# RoverWing-V1_3sch.net
KiCad netlist of a schematic drawn in EAGLE
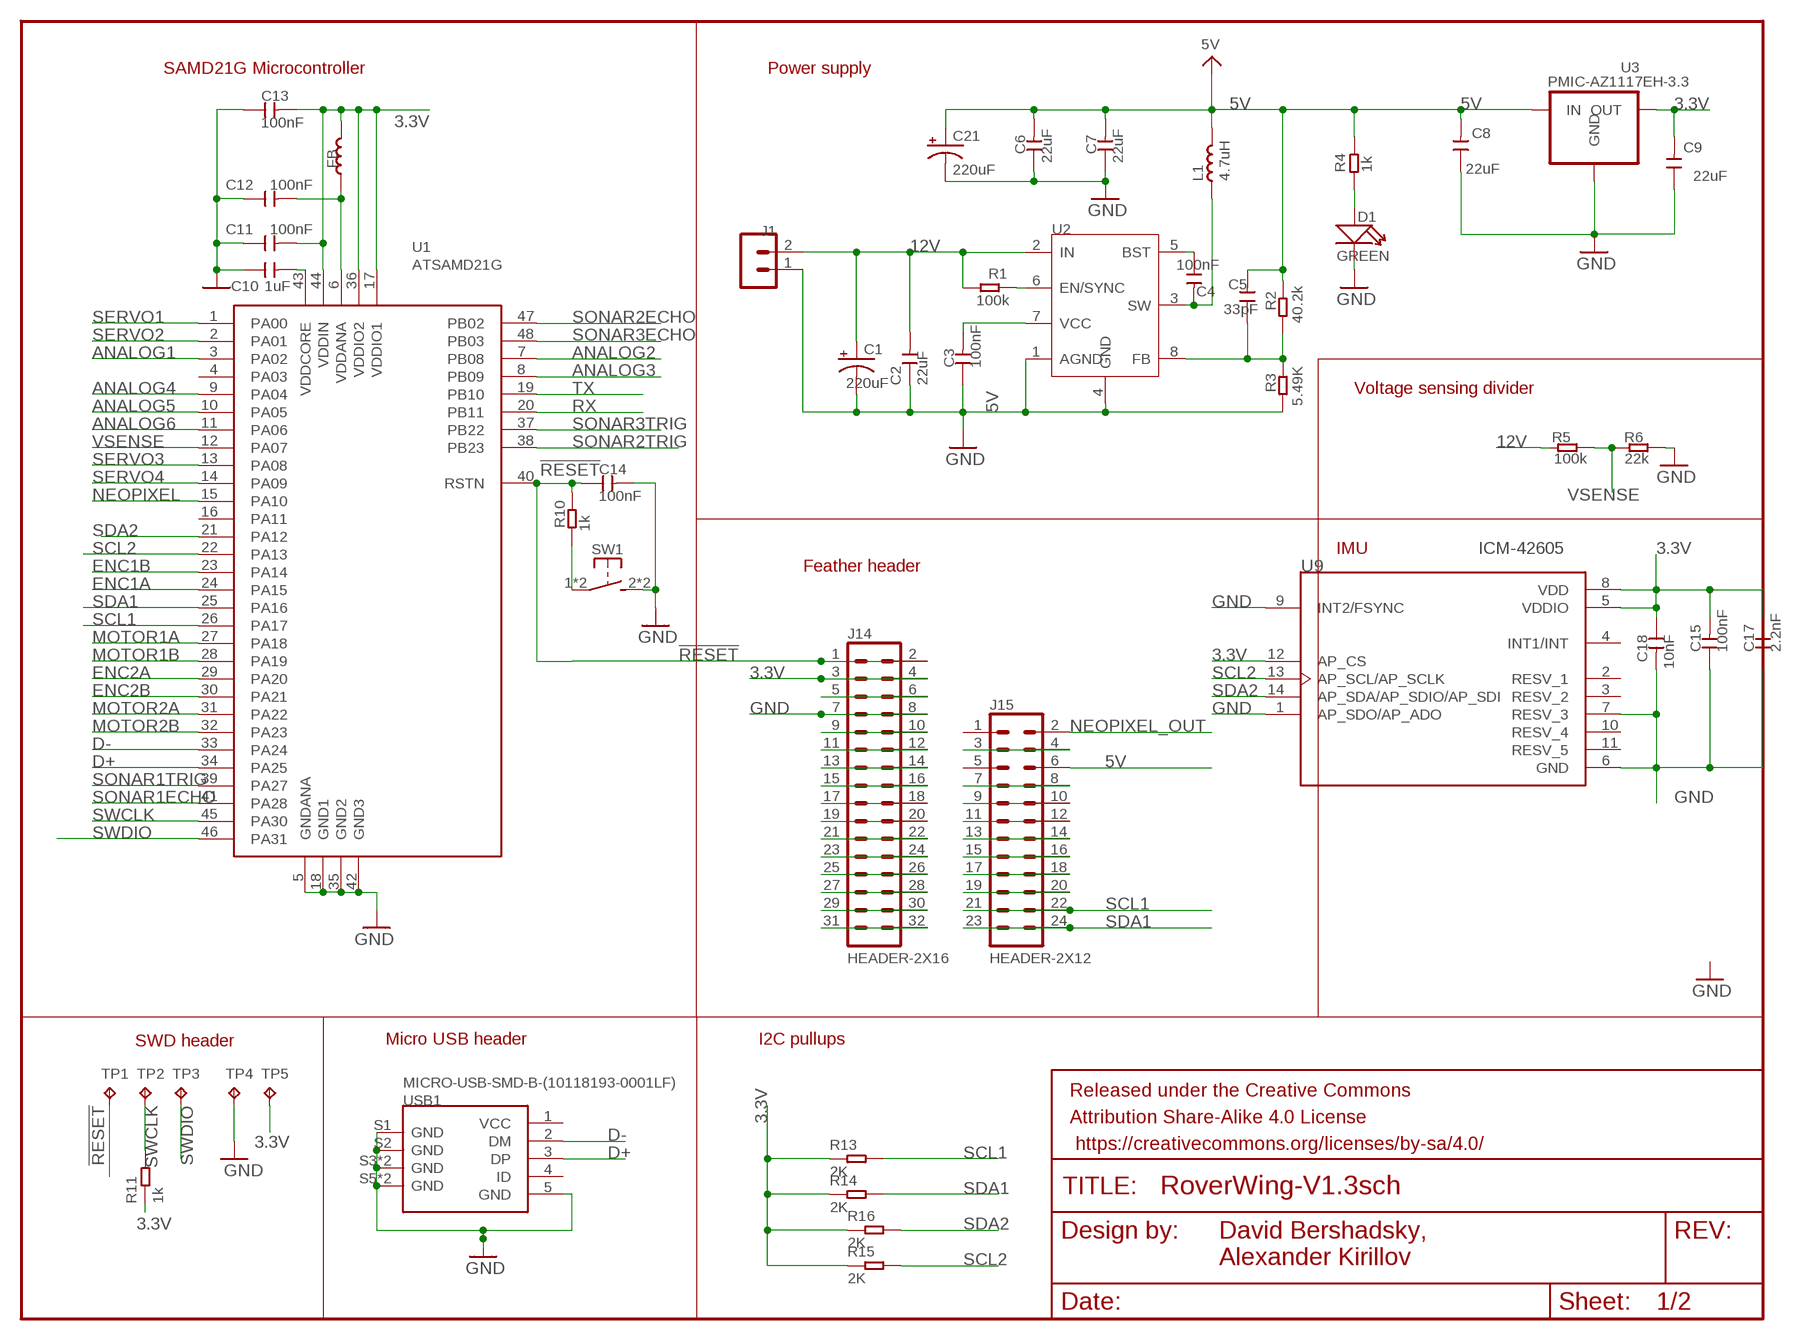
[diagram p0: schematic, sheet 1]
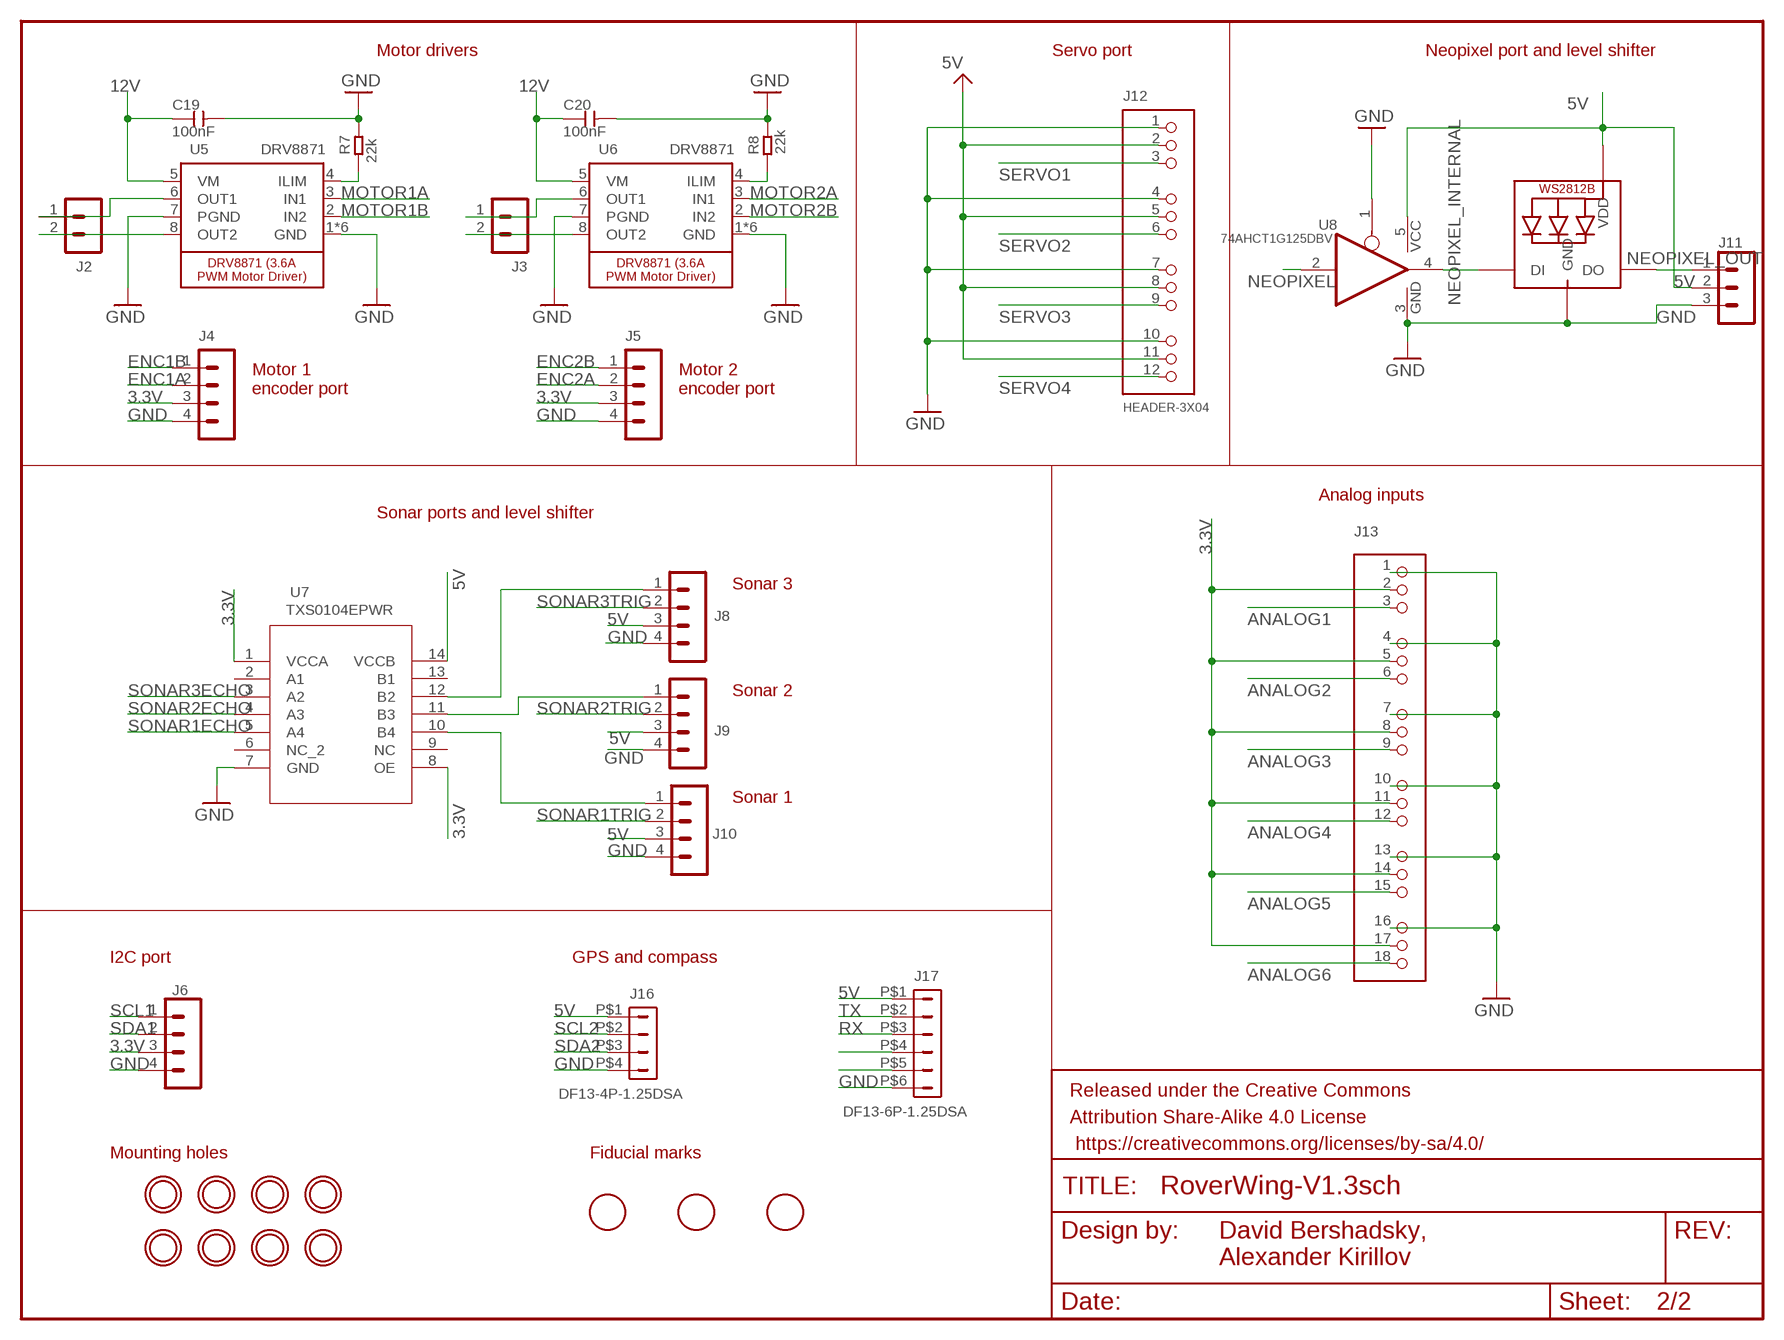
[diagram p1: schematic, sheet 2]

(export (version "E")
  (design (tool "Eeschema 10.0.6"))
  (components
    (comp (ref "C19")
      (value "100nF")
      (footprint "eagle-import:0805")
      (libsource (lib "eagle-import") (part "CAP-CERAMIC-SMD0805"))
    )
    (comp (ref "C20")
      (value "100nF")
      (footprint "eagle-import:0805")
      (libsource (lib "eagle-import") (part "CAP-CERAMIC-SMD0805"))
    )
    (comp (ref "D2")
      (value "WS2812B3535")
      (footprint "eagle-import:LED3535")
      (fields (field (name "MANUFACTURER") "Worldsemi") (field (name "PARTNO") "WS2812B-3535 "))
      (libsource (lib "eagle-import") (part "WS2812B3535"))
    )
    (comp (ref "FRAME1")
      (value "FRAME-LETTERNO_PACKAGE")
      (footprint "eagle-import:DUMMY")
      (libsource (lib "eagle-import") (part "FRAME-LETTERNO_PACKAGE"))
    )
    (comp (ref "J2")
      (value "HEADER-VH")
      (footprint "eagle-import:B2P-VH")
      (fields (field (name "PARTNO") "B2P-VH(LF)(SN)  "))
      (libsource (lib "eagle-import") (part "HEADER-VH"))
    )
    (comp (ref "J3")
      (value "HEADER-VH")
      (footprint "eagle-import:B2P-VH")
      (fields (field (name "PARTNO") "B2P-VH(LF)(SN)  "))
      (libsource (lib "eagle-import") (part "HEADER-VH"))
    )
    (comp (ref "J4")
      (value "HEADER-PH-4P")
      (footprint "eagle-import:B4B-PH-K")
      (fields (field (name "PARTNO") "B4B-PH-K-S(LF)(SN)"))
      (libsource (lib "eagle-import") (part "HEADER-PH-4P"))
    )
    (comp (ref "J5")
      (value "HEADER-PH-4P")
      (footprint "eagle-import:B4B-PH-K")
      (fields (field (name "PARTNO") "B4B-PH-K-S(LF)(SN)"))
      (libsource (lib "eagle-import") (part "HEADER-PH-4P"))
    )
    (comp (ref "J6")
      (value "HEADER-PH-4P")
      (footprint "eagle-import:B4B-PH-K")
      (fields (field (name "PARTNO") "B4B-PH-K-S(LF)(SN)"))
      (libsource (lib "eagle-import") (part "HEADER-PH-4P"))
    )
    (comp (ref "J8")
      (value "HEADER-PH-4P")
      (footprint "eagle-import:B4B-PH-K")
      (fields (field (name "PARTNO") "B4B-PH-K-S(LF)(SN)"))
      (libsource (lib "eagle-import") (part "HEADER-PH-4P"))
    )
    (comp (ref "J9")
      (value "HEADER-PH-4P")
      (footprint "eagle-import:B4B-PH-K")
      (fields (field (name "PARTNO") "B4B-PH-K-S(LF)(SN)"))
      (libsource (lib "eagle-import") (part "HEADER-PH-4P"))
    )
    (comp (ref "J10")
      (value "HEADER-PH-4P")
      (footprint "eagle-import:B4B-PH-K")
      (fields (field (name "PARTNO") "B4B-PH-K-S(LF)(SN)"))
      (libsource (lib "eagle-import") (part "HEADER-PH-4P"))
    )
    (comp (ref "J11")
      (value "HEADER-PH-3P")
      (footprint "eagle-import:B3B-PH-K")
      (fields (field (name "PARTNO") "B3B-PH-K-S(LF)(SN)"))
      (libsource (lib "eagle-import") (part "HEADER-PH-3P"))
    )
    (comp (ref "J12")
      (value "HEADER-3X04")
      (footprint "eagle-import:3X04")
      (libsource (lib "eagle-import") (part "HEADER-3X04"))
    )
    (comp (ref "J13")
      (value "HEADER-3X06\"")
      (footprint "eagle-import:3X06")
      (libsource (lib "eagle-import") (part "HEADER-3X06{dblquote}"))
    )
    (comp (ref "J16")
      (value "DF13-4P-1.25DSA")
      (footprint "eagle-import:DF13-4P-1.25DSA")
      (libsource (lib "eagle-import") (part "DF13-4P-1.25DSA"))
    )
    (comp (ref "J17")
      (value "DF13-6P-1.25DSA")
      (footprint "eagle-import:DF13-6P-1.25DSA")
      (libsource (lib "eagle-import") (part "DF13-6P-1.25DSA"))
    )
    (comp (ref "R7")
      (value "22k")
      (footprint "eagle-import:0805")
      (libsource (lib "eagle-import") (part "RES-SMD-0805"))
    )
    (comp (ref "R8")
      (value "22k")
      (footprint "eagle-import:0805")
      (libsource (lib "eagle-import") (part "RES-SMD-0805"))
    )
    (comp (ref "U$3")
      (value "MOUNTINGHOLE3.0_NPH")
      (footprint "eagle-import:MOUNTINGHOLE_3.0_NPH")
      (libsource (lib "eagle-import") (part "MOUNTINGHOLE3.0_NPH"))
    )
    (comp (ref "U$4")
      (value "MOUNTINGHOLE3.0_NPH")
      (footprint "eagle-import:MOUNTINGHOLE_3.0_NPH")
      (libsource (lib "eagle-import") (part "MOUNTINGHOLE3.0_NPH"))
    )
    (comp (ref "U$11")
      (value "FIDUCIAL")
      (footprint "eagle-import:FIDUCIAL_1MM")
      (libsource (lib "eagle-import") (part "FIDUCIAL"))
    )
    (comp (ref "U$13")
      (value "FIDUCIAL")
      (footprint "eagle-import:FIDUCIAL_1MM")
      (libsource (lib "eagle-import") (part "FIDUCIAL"))
    )
    (comp (ref "U$14")
      (value "MOUNTINGHOLE3.0_NPH")
      (footprint "eagle-import:MOUNTINGHOLE_3.0_NPH")
      (libsource (lib "eagle-import") (part "MOUNTINGHOLE3.0_NPH"))
    )
    (comp (ref "U$15")
      (value "MOUNTINGHOLE3.0_NPH")
      (footprint "eagle-import:MOUNTINGHOLE_3.0_NPH")
      (libsource (lib "eagle-import") (part "MOUNTINGHOLE3.0_NPH"))
    )
    (comp (ref "U$17")
      (value "FIDUCIAL")
      (footprint "eagle-import:FIDUCIAL_1MM")
      (libsource (lib "eagle-import") (part "FIDUCIAL"))
    )
    (comp (ref "U$24")
      (value "MOUNTINGHOLE3.0_NPH")
      (footprint "eagle-import:MOUNTINGHOLE_3.0_NPH")
      (libsource (lib "eagle-import") (part "MOUNTINGHOLE3.0_NPH"))
    )
    (comp (ref "U$25")
      (value "MOUNTINGHOLE3.0_NPH")
      (footprint "eagle-import:MOUNTINGHOLE_3.0_NPH")
      (libsource (lib "eagle-import") (part "MOUNTINGHOLE3.0_NPH"))
    )
    (comp (ref "U$26")
      (value "MOUNTINGHOLE3.0_NPH")
      (footprint "eagle-import:MOUNTINGHOLE_3.0_NPH")
      (libsource (lib "eagle-import") (part "MOUNTINGHOLE3.0_NPH"))
    )
    (comp (ref "U$27")
      (value "MOUNTINGHOLE3.0_NPH")
      (footprint "eagle-import:MOUNTINGHOLE_3.0_NPH")
      (libsource (lib "eagle-import") (part "MOUNTINGHOLE3.0_NPH"))
    )
    (comp (ref "U5")
      (value "DRV8871")
      (footprint "eagle-import:HSOP8")
      (fields (field (name "MANUFACTURER") "TEXAS INSTRUMENTS") (field (name "PARTNO") "DRV8871DDAR"))
      (libsource (lib "eagle-import") (part "DRV8871"))
    )
    (comp (ref "U6")
      (value "DRV8871")
      (footprint "eagle-import:HSOP8")
      (fields (field (name "MANUFACTURER") "TEXAS INSTRUMENTS") (field (name "PARTNO") "DRV8871DDAR"))
      (libsource (lib "eagle-import") (part "DRV8871"))
    )
    (comp (ref "U7")
      (value "TXS0104EPWR")
      (footprint "eagle-import:PW14")
      (fields (field (name "MANUFACTURER") "Texas Instruments"))
      (libsource (lib "eagle-import") (part "TXS0104EPWR"))
    )
    (comp (ref "U8")
      (value "74AHCT1G125DBV")
      (footprint "eagle-import:SOT23-5")
      (fields (field (name "PARTNO") "SN74AHCT1G125DBVR"))
      (libsource (lib "eagle-import") (part "741G125DBVAHCT"))
    )
    (comp (ref "C1")
      (value "220uF")
      (footprint "eagle-import:CAP-8X10.5")
      (libsource (lib "eagle-import") (part "CAP-POL-SMD-8X10.5"))
    )
    (comp (ref "C2")
      (value "22uF")
      (footprint "eagle-import:0805")
      (libsource (lib "eagle-import") (part "CAP-CERAMIC-SMD0805"))
    )
    (comp (ref "C3")
      (value "100nF")
      (footprint "eagle-import:0805")
      (libsource (lib "eagle-import") (part "CAP-CERAMIC-SMD0805"))
    )
    (comp (ref "C4")
      (value "100nF")
      (footprint "eagle-import:0805")
      (libsource (lib "eagle-import") (part "CAP-CERAMIC-SMD0805"))
    )
    (comp (ref "C5")
      (value "33pF")
      (footprint "eagle-import:0805")
      (libsource (lib "eagle-import") (part "CAP-CERAMIC-SMD0805"))
    )
    (comp (ref "C6")
      (value "22uF")
      (footprint "eagle-import:0805")
      (libsource (lib "eagle-import") (part "CAP-CERAMIC-SMD0805"))
    )
    (comp (ref "C7")
      (value "22uF")
      (footprint "eagle-import:0805")
      (libsource (lib "eagle-import") (part "CAP-CERAMIC-SMD0805"))
    )
    (comp (ref "C8")
      (value "22uF")
      (footprint "eagle-import:0805")
      (libsource (lib "eagle-import") (part "CAP-CERAMIC-SMD0805"))
    )
    (comp (ref "C9")
      (value "22uF")
      (footprint "eagle-import:0805")
      (libsource (lib "eagle-import") (part "CAP-CERAMIC-SMD0805"))
    )
    (comp (ref "C10")
      (value "1uF")
      (footprint "eagle-import:0805")
      (libsource (lib "eagle-import") (part "CAP-CERAMIC-SMD0805"))
    )
    (comp (ref "C11")
      (value "100nF")
      (footprint "eagle-import:0805")
      (libsource (lib "eagle-import") (part "CAP-CERAMIC-SMD0805"))
    )
    (comp (ref "C12")
      (value "100nF")
      (footprint "eagle-import:0805")
      (libsource (lib "eagle-import") (part "CAP-CERAMIC-SMD0805"))
    )
    (comp (ref "C13")
      (value "100nF")
      (footprint "eagle-import:0805")
      (libsource (lib "eagle-import") (part "CAP-CERAMIC-SMD0805"))
    )
    (comp (ref "C14")
      (value "100nF")
      (footprint "eagle-import:0805")
      (libsource (lib "eagle-import") (part "CAP-CERAMIC-SMD0805"))
    )
    (comp (ref "C15")
      (value "100nF")
      (footprint "eagle-import:0805")
      (libsource (lib "eagle-import") (part "CAP-CERAMIC-SMD0805"))
    )
    (comp (ref "C17")
      (value "2.2nF")
      (footprint "eagle-import:0805")
      (libsource (lib "eagle-import") (part "CAP-CERAMIC-SMD0805"))
    )
    (comp (ref "C18")
      (value "10nF")
      (footprint "eagle-import:0805")
      (libsource (lib "eagle-import") (part "CAP-CERAMIC-SMD0805"))
    )
    (comp (ref "C21")
      (value "220uF")
      (footprint "eagle-import:CAP-6.3X5.4")
      (fields (field (name "PARTNO") "CS1E470M-CRE54 "))
      (libsource (lib "eagle-import") (part "CAP-POL-SMD-6.3X5.4"))
    )
    (comp (ref "D1")
      (value "GREEN")
      (footprint "eagle-import:LED-0805")
      (libsource (lib "eagle-import") (part "SMD-LED-0805"))
    )
    (comp (ref "FB")
      (value "330R-1500MA")
      (footprint "eagle-import:0805")
      (fields (field (name "PARTNO") "BLM21PG331SN1D"))
      (libsource (lib "eagle-import") (part "SMD-FERRITE-BEAD-330R-1500MA(0805)"))
    )
    (comp (ref "FRAME2")
      (value "FRAME-LETTERNO_PACKAGE")
      (footprint "eagle-import:DUMMY")
      (libsource (lib "eagle-import") (part "FRAME-LETTERNO_PACKAGE"))
    )
    (comp (ref "J1")
      (value "HEADER-VH")
      (footprint "eagle-import:B2P-VH")
      (fields (field (name "PARTNO") "B2P-VH(LF)(SN)  "))
      (libsource (lib "eagle-import") (part "HEADER-VH"))
    )
    (comp (ref "J14")
      (value "HEADER-2X16")
      (footprint "eagle-import:2X16")
      (libsource (lib "eagle-import") (part "HEADER-2X16"))
    )
    (comp (ref "J15")
      (value "HEADER-2X12")
      (footprint "eagle-import:2X12")
      (libsource (lib "eagle-import") (part "HEADER-2X12"))
    )
    (comp (ref "L1")
      (value "4.7uH")
      (footprint "eagle-import:IND_TDK_7.1X6.5")
      (fields (field (name "MANUFACTURER") "TDK") (field (name "PARTNO") "SPM6530T-4R7M "))
      (libsource (lib "eagle-import") (part "IND-TDK-SPM6530T"))
    )
    (comp (ref "R1")
      (value "100k")
      (footprint "eagle-import:0805")
      (libsource (lib "eagle-import") (part "RES-SMD-0805"))
    )
    (comp (ref "R2")
      (value "40.2k")
      (footprint "eagle-import:0805")
      (libsource (lib "eagle-import") (part "RES-SMD-0805"))
    )
    (comp (ref "R3")
      (value "5.49K")
      (footprint "eagle-import:0805")
      (libsource (lib "eagle-import") (part "RES-SMD-0805"))
    )
    (comp (ref "R4")
      (value "1k")
      (footprint "eagle-import:0805")
      (libsource (lib "eagle-import") (part "RES-SMD-0805"))
    )
    (comp (ref "R5")
      (value "100k")
      (footprint "eagle-import:0805")
      (libsource (lib "eagle-import") (part "RES-SMD-0805"))
    )
    (comp (ref "R6")
      (value "22k")
      (footprint "eagle-import:0805")
      (libsource (lib "eagle-import") (part "RES-SMD-0805"))
    )
    (comp (ref "R10")
      (value "1k")
      (footprint "eagle-import:0805")
      (libsource (lib "eagle-import") (part "RES-SMD-0805"))
    )
    (comp (ref "R11")
      (value "1k")
      (footprint "eagle-import:0805")
      (libsource (lib "eagle-import") (part "RES-SMD-0805"))
    )
    (comp (ref "R13")
      (value "2K")
      (footprint "eagle-import:R0603")
      (fields (field (name "MPN") "RC0603FR-071K8L"))
      (libsource (lib "eagle-import") (part "SMD-RES-1.8K-1%-1/10W(0603)"))
    )
    (comp (ref "R14")
      (value "2K")
      (footprint "eagle-import:R0603")
      (fields (field (name "MPN") "RC0603FR-071K8L"))
      (libsource (lib "eagle-import") (part "SMD-RES-1.8K-1%-1/10W(0603)"))
    )
    (comp (ref "R15")
      (value "2K")
      (footprint "eagle-import:R0603")
      (fields (field (name "MPN") "RC0603FR-071K8L"))
      (libsource (lib "eagle-import") (part "SMD-RES-1.8K-1%-1/10W(0603)"))
    )
    (comp (ref "R16")
      (value "2K")
      (footprint "eagle-import:R0603")
      (fields (field (name "MPN") "RC0603FR-071K8L"))
      (libsource (lib "eagle-import") (part "SMD-RES-1.8K-1%-1/10W(0603)"))
    )
    (comp (ref "SW1")
      (value "SW-TACTILE-4.5X4.5_SMD")
      (footprint "eagle-import:TL3305")
      (fields (field (name "MANUFACTURER") "BRIGHT") (field (name "PARTNO") "TSA453G38-250 "))
      (libsource (lib "eagle-import") (part "SW-TACTILE-4.5X4.5_SMD"))
    )
    (comp (ref "TP1")
      (value "TPTP15R")
      (footprint "eagle-import:TP15R")
      (libsource (lib "eagle-import") (part "TPTP15R"))
    )
    (comp (ref "TP2")
      (value "TPTP15R")
      (footprint "eagle-import:TP15R")
      (libsource (lib "eagle-import") (part "TPTP15R"))
    )
    (comp (ref "TP3")
      (value "TPTP15R")
      (footprint "eagle-import:TP15R")
      (libsource (lib "eagle-import") (part "TPTP15R"))
    )
    (comp (ref "TP4")
      (value "TPTP15R")
      (footprint "eagle-import:TP15R")
      (libsource (lib "eagle-import") (part "TPTP15R"))
    )
    (comp (ref "TP5")
      (value "TPTP15R")
      (footprint "eagle-import:TP15R")
      (libsource (lib "eagle-import") (part "TPTP15R"))
    )
    (comp (ref "U1")
      (value "ATSAMD21G")
      (footprint "eagle-import:TQFP-48-EDITED")
      (fields (field (name "MANUFACTURER") "Microchip Technology") (field (name "PARTNO") "ATSAMD21G18A-AU"))
      (libsource (lib "eagle-import") (part "ATSAMD21G"))
    )
    (comp (ref "U2")
      (value "MP2225")
      (footprint "eagle-import:SOT-23-8")
      (fields (field (name "MANUFACTURER") "Monolithic Power Systems") (field (name "PARTNO") "MP2225GJ"))
      (libsource (lib "eagle-import") (part "PMIC-MP2225"))
    )
    (comp (ref "U3")
      (value "PMIC-AZ1117EH-3.3")
      (footprint "eagle-import:SOT223")
      (fields (field (name "PARTNO") "AZ1117EH-3.3TRG1"))
      (libsource (lib "eagle-import") (part "PMIC-AZ1117EH-3.3"))
    )
    (comp (ref "U9")
      (value "ICM-42605")
      (footprint "eagle-import:PQFN50P300X250X97-14N")
      (fields (field (name "DIGI-KEY_PART_NUMBER") "1428-1152-1-ND") (field (name "MF") "TDK InvenSense"))
      (libsource (lib "eagle-import") (part "ICM-42605"))
    )
    (comp (ref "USB1")
      (value "MICRO-USB-SMD-B-(10118193-0001LF)")
      (footprint "eagle-import:MICRO-USB5+6P-SMD-0.65-B")
      (fields (field (name "MANUFACTURER") "Amphenol ICC") (field (name "PARTNO") "10118193-0001LF"))
      (libsource (lib "eagle-import") (part "MICRO-USB-SMD-B-(10118193-0001LF)"))
    )
  )
  (nets
    (net (code "1") (name "3.3V") (class "Default")
      (node (ref "C11") (pin "2") (pinfunction "2_2") (pintype "passive"))
      (node (ref "C13") (pin "2") (pinfunction "2_2") (pintype "passive"))
      (node (ref "C15") (pin "2") (pinfunction "2_2") (pintype "passive"))
      (node (ref "C17") (pin "2") (pinfunction "2_2") (pintype "passive"))
      (node (ref "C18") (pin "1") (pinfunction "1_1") (pintype "passive"))
      (node (ref "C9") (pin "2") (pinfunction "2_2") (pintype "passive"))
      (node (ref "FB") (pin "2") (pinfunction "2_2") (pintype "passive"))
      (node (ref "J13") (pin "11") (pinfunction "11_11") (pintype "passive"))
      (node (ref "J13") (pin "14") (pinfunction "14_14") (pintype "passive"))
      (node (ref "J13") (pin "17") (pinfunction "17_17") (pintype "passive"))
      (node (ref "J13") (pin "2") (pinfunction "2_2") (pintype "passive"))
      (node (ref "J13") (pin "5") (pinfunction "5_5") (pintype "passive"))
      (node (ref "J13") (pin "8") (pinfunction "8_8") (pintype "passive"))
      (node (ref "J14") (pin "3") (pinfunction "3_3") (pintype "passive"))
      (node (ref "J14") (pin "4") (pinfunction "4_4") (pintype "passive"))
      (node (ref "J4") (pin "3") (pinfunction "3_3") (pintype "passive"))
      (node (ref "J5") (pin "3") (pinfunction "3_3") (pintype "passive"))
      (node (ref "J6") (pin "3") (pinfunction "3_3") (pintype "passive"))
      (node (ref "R11") (pin "1") (pinfunction "1_1") (pintype "passive"))
      (node (ref "R13") (pin "1") (pinfunction "1_1") (pintype "passive"))
      (node (ref "R14") (pin "1") (pinfunction "1_1") (pintype "passive"))
      (node (ref "R15") (pin "1") (pinfunction "1_1") (pintype "passive"))
      (node (ref "R16") (pin "1") (pinfunction "1_1") (pintype "passive"))
      (node (ref "TP5") (pin "TP") (pinfunction "TP_TP") (pintype "input"))
      (node (ref "U1") (pin "17") (pinfunction "VDDIO1_17") (pintype "power_in"))
      (node (ref "U1") (pin "36") (pinfunction "VDDIO2_36") (pintype "power_in"))
      (node (ref "U1") (pin "44") (pinfunction "VDDIN_44") (pintype "power_in"))
      (node (ref "U3") (pin "2") (pinfunction "OUT_2") (pintype "output"))
      (node (ref "U3") (pin "4") (pinfunction "OUT_4") (pintype "output"))
      (node (ref "U7") (pin "1") (pinfunction "VCCA_1") (pintype "power_in"))
      (node (ref "U7") (pin "8") (pinfunction "OE_8") (pintype "output"))
      (node (ref "U9") (pin "12") (pinfunction "AP_CS_12") (pintype "input"))
      (node (ref "U9") (pin "5") (pinfunction "VDDIO_5") (pintype "power_in"))
      (node (ref "U9") (pin "8") (pinfunction "VDD_8") (pintype "power_in"))
    )
    (net (code "2") (name "5V") (class "Default")
      (node (ref "C21") (pin "+") (pinfunction "+_+") (pintype "passive"))
      (node (ref "C5") (pin "2") (pinfunction "2_2") (pintype "passive"))
      (node (ref "C6") (pin "2") (pinfunction "2_2") (pintype "passive"))
      (node (ref "C7") (pin "2") (pinfunction "2_2") (pintype "passive"))
      (node (ref "C8") (pin "2") (pinfunction "2_2") (pintype "passive"))
      (node (ref "D2") (pin "3") (pinfunction "VDD_3") (pintype "power_in"))
      (node (ref "J10") (pin "3") (pinfunction "3_3") (pintype "passive"))
      (node (ref "J11") (pin "2") (pinfunction "2_2") (pintype "passive"))
      (node (ref "J12") (pin "11") (pinfunction "11_11") (pintype "passive"))
      (node (ref "J12") (pin "2") (pinfunction "2_2") (pintype "passive"))
      (node (ref "J12") (pin "5") (pinfunction "5_5") (pintype "passive"))
      (node (ref "J12") (pin "8") (pinfunction "8_8") (pintype "passive"))
      (node (ref "J15") (pin "6") (pinfunction "6_6") (pintype "passive"))
      (node (ref "J16") (pin "P$1") (pinfunction "1_P$1") (pintype "passive"))
      (node (ref "J17") (pin "P$1") (pinfunction "1_P$1") (pintype "passive"))
      (node (ref "J8") (pin "3") (pinfunction "3_3") (pintype "passive"))
      (node (ref "J9") (pin "3") (pinfunction "3_3") (pintype "passive"))
      (node (ref "L1") (pin "2") (pinfunction "2_2") (pintype "passive"))
      (node (ref "R2") (pin "1") (pinfunction "1_1") (pintype "passive"))
      (node (ref "R4") (pin "2") (pinfunction "2_2") (pintype "passive"))
      (node (ref "U3") (pin "3") (pinfunction "IN_3") (pintype "input"))
      (node (ref "U7") (pin "14") (pinfunction "VCCB_14") (pintype "power_in"))
      (node (ref "U8") (pin "5") (pinfunction "VCC_5") (pintype "power_in"))
    )
    (net (code "3") (name "12V") (class "Default")
      (node (ref "C1") (pin "+") (pinfunction "+_+") (pintype "passive"))
      (node (ref "C19") (pin "1") (pinfunction "1_1") (pintype "passive"))
      (node (ref "C2") (pin "2") (pinfunction "2_2") (pintype "passive"))
      (node (ref "C20") (pin "1") (pinfunction "1_1") (pintype "passive"))
      (node (ref "J1") (pin "2") (pinfunction "2_2") (pintype "passive"))
      (node (ref "R1") (pin "2") (pinfunction "2_2") (pintype "passive"))
      (node (ref "R5") (pin "2") (pinfunction "2_2") (pintype "passive"))
      (node (ref "U2") (pin "2") (pinfunction "IN_2") (pintype "bidirectional"))
      (node (ref "U5") (pin "5") (pinfunction "VM_5") (pintype "power_in"))
      (node (ref "U6") (pin "5") (pinfunction "VM_5") (pintype "power_in"))
    )
    (net (code "4") (name "ANALOG1") (class "Default")
      (node (ref "J13") (pin "3") (pinfunction "3_3") (pintype "passive"))
      (node (ref "U1") (pin "3") (pinfunction "PA02_3") (pintype "bidirectional"))
    )
    (net (code "5") (name "ANALOG2") (class "Default")
      (node (ref "J13") (pin "6") (pinfunction "6_6") (pintype "passive"))
      (node (ref "U1") (pin "7") (pinfunction "PB08_7") (pintype "bidirectional"))
    )
    (net (code "6") (name "ANALOG3") (class "Default")
      (node (ref "J13") (pin "9") (pinfunction "9_9") (pintype "passive"))
      (node (ref "U1") (pin "8") (pinfunction "PB09_8") (pintype "bidirectional"))
    )
    (net (code "7") (name "ANALOG4") (class "Default")
      (node (ref "J13") (pin "12") (pinfunction "12_12") (pintype "passive"))
      (node (ref "U1") (pin "9") (pinfunction "PA04_9") (pintype "bidirectional"))
    )
    (net (code "8") (name "ANALOG5") (class "Default")
      (node (ref "J13") (pin "15") (pinfunction "15_15") (pintype "passive"))
      (node (ref "U1") (pin "10") (pinfunction "PA05_10") (pintype "bidirectional"))
    )
    (net (code "9") (name "ANALOG6") (class "Default")
      (node (ref "J13") (pin "18") (pinfunction "18_18") (pintype "passive"))
      (node (ref "U1") (pin "11") (pinfunction "PA06_11") (pintype "bidirectional"))
    )
    (net (code "10") (name "D+") (class "Default")
      (node (ref "U1") (pin "34") (pinfunction "PA25_34") (pintype "bidirectional"))
      (node (ref "USB1") (pin "3") (pinfunction "DP_3") (pintype "bidirectional"))
    )
    (net (code "11") (name "D-") (class "Default")
      (node (ref "U1") (pin "33") (pinfunction "PA24_33") (pintype "bidirectional"))
      (node (ref "USB1") (pin "2") (pinfunction "DM_2") (pintype "bidirectional"))
    )
    (net (code "12") (name "ENC1A") (class "Default")
      (node (ref "J4") (pin "2") (pinfunction "2_2") (pintype "passive"))
      (node (ref "U1") (pin "24") (pinfunction "PA15_24") (pintype "bidirectional"))
    )
    (net (code "13") (name "ENC1B") (class "Default")
      (node (ref "J4") (pin "1") (pinfunction "1_1") (pintype "passive"))
      (node (ref "U1") (pin "23") (pinfunction "PA14_23") (pintype "bidirectional"))
    )
    (net (code "14") (name "ENC2A") (class "Default")
      (node (ref "J5") (pin "2") (pinfunction "2_2") (pintype "passive"))
      (node (ref "U1") (pin "29") (pinfunction "PA20_29") (pintype "bidirectional"))
    )
    (net (code "15") (name "ENC2B") (class "Default")
      (node (ref "J5") (pin "1") (pinfunction "1_1") (pintype "passive"))
      (node (ref "U1") (pin "30") (pinfunction "PA21_30") (pintype "bidirectional"))
    )
    (net (code "16") (name "GND") (class "Default")
      (node (ref "C1") (pin "-") (pinfunction "-_-") (pintype "passive"))
      (node (ref "C10") (pin "1") (pinfunction "1_1") (pintype "passive"))
      (node (ref "C11") (pin "1") (pinfunction "1_1") (pintype "passive"))
      (node (ref "C12") (pin "1") (pinfunction "1_1") (pintype "passive"))
      (node (ref "C13") (pin "1") (pinfunction "1_1") (pintype "passive"))
      (node (ref "C14") (pin "2") (pinfunction "2_2") (pintype "passive"))
      (node (ref "C15") (pin "1") (pinfunction "1_1") (pintype "passive"))
      (node (ref "C17") (pin "1") (pinfunction "1_1") (pintype "passive"))
      (node (ref "C18") (pin "2") (pinfunction "2_2") (pintype "passive"))
      (node (ref "C19") (pin "2") (pinfunction "2_2") (pintype "passive"))
      (node (ref "C2") (pin "1") (pinfunction "1_1") (pintype "passive"))
      (node (ref "C20") (pin "2") (pinfunction "2_2") (pintype "passive"))
      (node (ref "C21") (pin "-") (pinfunction "-_-") (pintype "passive"))
      (node (ref "C3") (pin "1") (pinfunction "1_1") (pintype "passive"))
      (node (ref "C6") (pin "1") (pinfunction "1_1") (pintype "passive"))
      (node (ref "C7") (pin "1") (pinfunction "1_1") (pintype "passive"))
      (node (ref "C8") (pin "1") (pinfunction "1_1") (pintype "passive"))
      (node (ref "C9") (pin "1") (pinfunction "1_1") (pintype "passive"))
      (node (ref "D1") (pin "-") (pinfunction "-_-") (pintype "passive"))
      (node (ref "D2") (pin "1") (pinfunction "GND_1") (pintype "power_in"))
      (node (ref "J1") (pin "1") (pinfunction "1_1") (pintype "passive"))
      (node (ref "J10") (pin "4") (pinfunction "4_4") (pintype "passive"))
      (node (ref "J11") (pin "3") (pinfunction "3_3") (pintype "passive"))
      (node (ref "J12") (pin "1") (pinfunction "1_1") (pintype "passive"))
      (node (ref "J12") (pin "10") (pinfunction "10_10") (pintype "passive"))
      (node (ref "J12") (pin "4") (pinfunction "4_4") (pintype "passive"))
      (node (ref "J12") (pin "7") (pinfunction "7_7") (pintype "passive"))
      (node (ref "J13") (pin "1") (pinfunction "1_1") (pintype "passive"))
      (node (ref "J13") (pin "10") (pinfunction "10_10") (pintype "passive"))
      (node (ref "J13") (pin "13") (pinfunction "13_13") (pintype "passive"))
      (node (ref "J13") (pin "16") (pinfunction "16_16") (pintype "passive"))
      (node (ref "J13") (pin "4") (pinfunction "4_4") (pintype "passive"))
      (node (ref "J13") (pin "7") (pinfunction "7_7") (pintype "passive"))
      (node (ref "J14") (pin "7") (pinfunction "7_7") (pintype "passive"))
      (node (ref "J14") (pin "8") (pinfunction "8_8") (pintype "passive"))
      (node (ref "J16") (pin "P$4") (pinfunction "4_P$4") (pintype "passive"))
      (node (ref "J17") (pin "P$6") (pinfunction "6_P$6") (pintype "passive"))
      (node (ref "J4") (pin "4") (pinfunction "4_4") (pintype "passive"))
      (node (ref "J5") (pin "4") (pinfunction "4_4") (pintype "passive"))
      (node (ref "J6") (pin "4") (pinfunction "4_4") (pintype "passive"))
      (node (ref "J8") (pin "4") (pinfunction "4_4") (pintype "passive"))
      (node (ref "J9") (pin "4") (pinfunction "4_4") (pintype "passive"))
      (node (ref "R3") (pin "2") (pinfunction "2_2") (pintype "passive"))
      (node (ref "R6") (pin "2") (pinfunction "2_2") (pintype "passive"))
      (node (ref "R7") (pin "2") (pinfunction "2_2") (pintype "passive"))
      (node (ref "R8") (pin "2") (pinfunction "2_2") (pintype "passive"))
      (node (ref "SW1") (pin "2") (pinfunction "S1_2") (pintype "passive"))
      (node (ref "SW1") (pin "3") (pinfunction "S1_3") (pintype "passive"))
      (node (ref "TP4") (pin "TP") (pinfunction "TP_TP") (pintype "input"))
      (node (ref "U1") (pin "18") (pinfunction "GND1_18") (pintype "power_in"))
      (node (ref "U1") (pin "35") (pinfunction "GND2_35") (pintype "power_in"))
      (node (ref "U1") (pin "42") (pinfunction "GND3_42") (pintype "power_in"))
      (node (ref "U1") (pin "5") (pinfunction "GNDANA_5") (pintype "power_in"))
      (node (ref "U2") (pin "1") (pinfunction "AGND_1") (pintype "bidirectional"))
      (node (ref "U2") (pin "4") (pinfunction "GND_4") (pintype "bidirectional"))
      (node (ref "U3") (pin "1") (pinfunction "GND_1") (pintype "power_in"))
      (node (ref "U5") (pin "1") (pinfunction "GND_1") (pintype "power_in"))
      (node (ref "U5") (pin "7") (pinfunction "PGND_7") (pintype "power_in"))
      (node (ref "U5") (pin "GND") (pinfunction "GND_GND") (pintype "power_in"))
      (node (ref "U5") (pin "P$1") (pinfunction "GND_P$1") (pintype "power_in"))
      (node (ref "U5") (pin "P$2") (pinfunction "GND_P$2") (pintype "power_in"))
      (node (ref "U5") (pin "P$3") (pinfunction "GND_P$3") (pintype "power_in"))
      (node (ref "U5") (pin "P$4") (pinfunction "GND_P$4") (pintype "power_in"))
      (node (ref "U6") (pin "1") (pinfunction "GND_1") (pintype "power_in"))
      (node (ref "U6") (pin "7") (pinfunction "PGND_7") (pintype "power_in"))
      (node (ref "U6") (pin "GND") (pinfunction "GND_GND") (pintype "power_in"))
      (node (ref "U6") (pin "P$1") (pinfunction "GND_P$1") (pintype "power_in"))
      (node (ref "U6") (pin "P$2") (pinfunction "GND_P$2") (pintype "power_in"))
      (node (ref "U6") (pin "P$3") (pinfunction "GND_P$3") (pintype "power_in"))
      (node (ref "U6") (pin "P$4") (pinfunction "GND_P$4") (pintype "power_in"))
      (node (ref "U7") (pin "7") (pinfunction "GND_7") (pintype "power_in"))
      (node (ref "U8") (pin "1") (pinfunction "OE_1") (pintype "input"))
      (node (ref "U8") (pin "3") (pinfunction "GND_3") (pintype "power_in"))
      (node (ref "U9") (pin "1") (pinfunction "AP_SDO/AP_ADO_1") (pintype "output"))
      (node (ref "U9") (pin "6") (pinfunction "GND_6") (pintype "power_in"))
      (node (ref "U9") (pin "7") (pinfunction "RESV_3_7") (pintype "bidirectional"))
      (node (ref "U9") (pin "9") (pinfunction "INT2/FSYNC_9") (pintype "bidirectional"))
      (node (ref "USB1") (pin "5") (pinfunction "GND_5") (pintype "bidirectional"))
      (node (ref "USB1") (pin "S1") (pinfunction "GND_S1") (pintype "bidirectional"))
      (node (ref "USB1") (pin "S2") (pinfunction "GND_S2") (pintype "bidirectional"))
      (node (ref "USB1") (pin "S3") (pinfunction "GND_S3") (pintype "bidirectional"))
      (node (ref "USB1") (pin "S4") (pinfunction "GND_S4") (pintype "bidirectional"))
      (node (ref "USB1") (pin "S5") (pinfunction "GND_S5") (pintype "bidirectional"))
      (node (ref "USB1") (pin "S6") (pinfunction "GND_S6") (pintype "bidirectional"))
    )
    (net (code "17") (name "MOTOR1A") (class "Default")
      (node (ref "U1") (pin "27") (pinfunction "PA18_27") (pintype "bidirectional"))
      (node (ref "U5") (pin "3") (pinfunction "IN1_3") (pintype "input"))
    )
    (net (code "18") (name "MOTOR1B") (class "Default")
      (node (ref "U1") (pin "28") (pinfunction "PA19_28") (pintype "bidirectional"))
      (node (ref "U5") (pin "2") (pinfunction "IN2_2") (pintype "input"))
    )
    (net (code "19") (name "MOTOR2A") (class "Default")
      (node (ref "U1") (pin "31") (pinfunction "PA22_31") (pintype "bidirectional"))
      (node (ref "U6") (pin "3") (pinfunction "IN1_3") (pintype "input"))
    )
    (net (code "20") (name "MOTOR2B") (class "Default")
      (node (ref "U1") (pin "32") (pinfunction "PA23_32") (pintype "bidirectional"))
      (node (ref "U6") (pin "2") (pinfunction "IN2_2") (pintype "input"))
    )
    (net (code "21") (name "NEOPIXEL") (class "Default")
      (node (ref "U1") (pin "15") (pinfunction "PA10_15") (pintype "bidirectional"))
      (node (ref "U8") (pin "2") (pinfunction "I_2") (pintype "input"))
    )
    (net (code "22") (name "NEOPIXEL_INTERNAL") (class "Default")
      (node (ref "D2") (pin "2") (pinfunction "DI_2") (pintype "input"))
      (node (ref "U8") (pin "4") (pinfunction "O_4") (pintype "tri_state"))
    )
    (net (code "23") (name "NEOPIXEL_OUT") (class "Default")
      (node (ref "D2") (pin "4") (pinfunction "DO_4") (pintype "output"))
      (node (ref "J11") (pin "1") (pinfunction "1_1") (pintype "passive"))
      (node (ref "J15") (pin "2") (pinfunction "2_2") (pintype "passive"))
    )
    (net (code "24") (name "Net-(D1-Pad+)") (class "Default")
      (node (ref "D1") (pin "+") (pinfunction "+_+") (pintype "passive"))
      (node (ref "R4") (pin "1") (pinfunction "1_1") (pintype "passive"))
    )
    (net (code "25") (name "Net-(J14-Pad5)") (class "Default")
      (node (ref "J14") (pin "5") (pinfunction "5_5") (pintype "passive"))
      (node (ref "J14") (pin "6") (pinfunction "6_6") (pintype "passive"))
    )
    (net (code "26") (name "Net-(J14-Pad10)") (class "Default")
      (node (ref "J14") (pin "10") (pinfunction "10_10") (pintype "passive"))
      (node (ref "J14") (pin "9") (pinfunction "9_9") (pintype "passive"))
    )
    (net (code "27") (name "Net-(J14-Pad11)") (class "Default")
      (node (ref "J14") (pin "11") (pinfunction "11_11") (pintype "passive"))
      (node (ref "J14") (pin "12") (pinfunction "12_12") (pintype "passive"))
    )
    (net (code "28") (name "Net-(J14-Pad13)") (class "Default")
      (node (ref "J14") (pin "13") (pinfunction "13_13") (pintype "passive"))
      (node (ref "J14") (pin "14") (pinfunction "14_14") (pintype "passive"))
    )
    (net (code "29") (name "Net-(J14-Pad15)") (class "Default")
      (node (ref "J14") (pin "15") (pinfunction "15_15") (pintype "passive"))
      (node (ref "J14") (pin "16") (pinfunction "16_16") (pintype "passive"))
    )
    (net (code "30") (name "Net-(J14-Pad17)") (class "Default")
      (node (ref "J14") (pin "17") (pinfunction "17_17") (pintype "passive"))
      (node (ref "J14") (pin "18") (pinfunction "18_18") (pintype "passive"))
    )
    (net (code "31") (name "Net-(J14-Pad19)") (class "Default")
      (node (ref "J14") (pin "19") (pinfunction "19_19") (pintype "passive"))
      (node (ref "J14") (pin "20") (pinfunction "20_20") (pintype "passive"))
    )
    (net (code "32") (name "Net-(J14-Pad21)") (class "Default")
      (node (ref "J14") (pin "21") (pinfunction "21_21") (pintype "passive"))
      (node (ref "J14") (pin "22") (pinfunction "22_22") (pintype "passive"))
    )
    (net (code "33") (name "Net-(J14-Pad23)") (class "Default")
      (node (ref "J14") (pin "23") (pinfunction "23_23") (pintype "passive"))
      (node (ref "J14") (pin "24") (pinfunction "24_24") (pintype "passive"))
    )
    (net (code "34") (name "Net-(J14-Pad25)") (class "Default")
      (node (ref "J14") (pin "25") (pinfunction "25_25") (pintype "passive"))
      (node (ref "J14") (pin "26") (pinfunction "26_26") (pintype "passive"))
    )
    (net (code "35") (name "Net-(J14-Pad27)") (class "Default")
      (node (ref "J14") (pin "27") (pinfunction "27_27") (pintype "passive"))
      (node (ref "J14") (pin "28") (pinfunction "28_28") (pintype "passive"))
    )
    (net (code "36") (name "Net-(J14-Pad29)") (class "Default")
      (node (ref "J14") (pin "29") (pinfunction "29_29") (pintype "passive"))
      (node (ref "J14") (pin "30") (pinfunction "30_30") (pintype "passive"))
    )
    (net (code "37") (name "Net-(J14-Pad31)") (class "Default")
      (node (ref "J14") (pin "31") (pinfunction "31_31") (pintype "passive"))
      (node (ref "J14") (pin "32") (pinfunction "32_32") (pintype "passive"))
    )
    (net (code "38") (name "Net-(J15-Pad3)") (class "Default")
      (node (ref "J15") (pin "3") (pinfunction "3_3") (pintype "passive"))
      (node (ref "J15") (pin "4") (pinfunction "4_4") (pintype "passive"))
    )
    (net (code "39") (name "Net-(J15-Pad7)") (class "Default")
      (node (ref "J15") (pin "7") (pinfunction "7_7") (pintype "passive"))
      (node (ref "J15") (pin "8") (pinfunction "8_8") (pintype "passive"))
    )
    (net (code "40") (name "Net-(J15-Pad10)") (class "Default")
      (node (ref "J15") (pin "10") (pinfunction "10_10") (pintype "passive"))
      (node (ref "J15") (pin "9") (pinfunction "9_9") (pintype "passive"))
    )
    (net (code "41") (name "Net-(J15-Pad11)") (class "Default")
      (node (ref "J15") (pin "11") (pinfunction "11_11") (pintype "passive"))
      (node (ref "J15") (pin "12") (pinfunction "12_12") (pintype "passive"))
    )
    (net (code "42") (name "Net-(J15-Pad13)") (class "Default")
      (node (ref "J15") (pin "13") (pinfunction "13_13") (pintype "passive"))
      (node (ref "J15") (pin "14") (pinfunction "14_14") (pintype "passive"))
    )
    (net (code "43") (name "Net-(J15-Pad15)") (class "Default")
      (node (ref "J15") (pin "15") (pinfunction "15_15") (pintype "passive"))
      (node (ref "J15") (pin "16") (pinfunction "16_16") (pintype "passive"))
    )
    (net (code "44") (name "Net-(J15-Pad17)") (class "Default")
      (node (ref "J15") (pin "17") (pinfunction "17_17") (pintype "passive"))
      (node (ref "J15") (pin "18") (pinfunction "18_18") (pintype "passive"))
    )
    (net (code "45") (name "Net-(J15-Pad19)") (class "Default")
      (node (ref "J15") (pin "19") (pinfunction "19_19") (pintype "passive"))
      (node (ref "J15") (pin "20") (pinfunction "20_20") (pintype "passive"))
    )
    (net (code "46") (name "Net-(R10-Pad1)") (class "Default")
      (node (ref "R10") (pin "1") (pinfunction "1_1") (pintype "passive"))
      (node (ref "SW1") (pin "1") (pinfunction "P1_1") (pintype "passive"))
      (node (ref "SW1") (pin "4") (pinfunction "P1_4") (pintype "passive"))
    )
    (net (code "47") (name "Net-(U1-VDDANA)") (class "Default")
      (node (ref "C12") (pin "2") (pinfunction "2_2") (pintype "passive"))
      (node (ref "FB") (pin "1") (pinfunction "1_1") (pintype "passive"))
      (node (ref "U1") (pin "6") (pinfunction "VDDANA_6") (pintype "power_in"))
    )
    (net (code "48") (name "Net-(U1-VDDCORE)") (class "Default")
      (node (ref "C10") (pin "2") (pinfunction "2_2") (pintype "passive"))
      (node (ref "U1") (pin "43") (pinfunction "VDDCORE_43") (pintype "power_in"))
    )
    (net (code "49") (name "Net-(U2-BST)") (class "Default")
      (node (ref "C4") (pin "1") (pinfunction "1_1") (pintype "passive"))
      (node (ref "U2") (pin "5") (pinfunction "BST_5") (pintype "bidirectional"))
    )
    (net (code "50") (name "Net-(U2-EN{slash}SYNC)") (class "Default")
      (node (ref "R1") (pin "1") (pinfunction "1_1") (pintype "passive"))
      (node (ref "U2") (pin "6") (pinfunction "EN/SYNC_6") (pintype "bidirectional"))
    )
    (net (code "51") (name "Net-(U2-FB)") (class "Default")
      (node (ref "C5") (pin "1") (pinfunction "1_1") (pintype "passive"))
      (node (ref "R2") (pin "2") (pinfunction "2_2") (pintype "passive"))
      (node (ref "R3") (pin "1") (pinfunction "1_1") (pintype "passive"))
      (node (ref "U2") (pin "8") (pinfunction "FB_8") (pintype "bidirectional"))
    )
    (net (code "52") (name "Net-(U2-SW)") (class "Default")
      (node (ref "C4") (pin "2") (pinfunction "2_2") (pintype "passive"))
      (node (ref "L1") (pin "1") (pinfunction "1_1") (pintype "passive"))
      (node (ref "U2") (pin "3") (pinfunction "SW_3") (pintype "bidirectional"))
    )
    (net (code "53") (name "Net-(U2-VCC)") (class "Default")
      (node (ref "C3") (pin "2") (pinfunction "2_2") (pintype "passive"))
      (node (ref "U2") (pin "7") (pinfunction "VCC_7") (pintype "bidirectional"))
    )
    (net (code "54") (name "Net-(U5-ILIM)") (class "Default")
      (node (ref "R7") (pin "1") (pinfunction "1_1") (pintype "passive"))
      (node (ref "U5") (pin "4") (pinfunction "ILIM_4") (pintype "input"))
    )
    (net (code "55") (name "Net-(U5-OUT1)") (class "Default")
      (node (ref "J2") (pin "1") (pinfunction "1_1") (pintype "passive"))
      (node (ref "U5") (pin "6") (pinfunction "OUT1_6") (pintype "output"))
    )
    (net (code "56") (name "Net-(U5-OUT2)") (class "Default")
      (node (ref "J2") (pin "2") (pinfunction "2_2") (pintype "passive"))
      (node (ref "U5") (pin "8") (pinfunction "OUT2_8") (pintype "output"))
    )
    (net (code "57") (name "Net-(U6-ILIM)") (class "Default")
      (node (ref "R8") (pin "1") (pinfunction "1_1") (pintype "passive"))
      (node (ref "U6") (pin "4") (pinfunction "ILIM_4") (pintype "input"))
    )
    (net (code "58") (name "Net-(U6-OUT1)") (class "Default")
      (node (ref "J3") (pin "1") (pinfunction "1_1") (pintype "passive"))
      (node (ref "U6") (pin "6") (pinfunction "OUT1_6") (pintype "output"))
    )
    (net (code "59") (name "Net-(U6-OUT2)") (class "Default")
      (node (ref "J3") (pin "2") (pinfunction "2_2") (pintype "passive"))
      (node (ref "U6") (pin "8") (pinfunction "OUT2_8") (pintype "output"))
    )
    (net (code "60") (name "Net-(U7-B2)") (class "Default")
      (node (ref "J8") (pin "1") (pinfunction "1_1") (pintype "passive"))
      (node (ref "U7") (pin "12") (pinfunction "B2_12") (pintype "bidirectional"))
    )
    (net (code "61") (name "Net-(U7-B3)") (class "Default")
      (node (ref "J9") (pin "1") (pinfunction "1_1") (pintype "passive"))
      (node (ref "U7") (pin "11") (pinfunction "B3_11") (pintype "bidirectional"))
    )
    (net (code "62") (name "Net-(U7-B4)") (class "Default")
      (node (ref "J10") (pin "1") (pinfunction "1_1") (pintype "passive"))
      (node (ref "U7") (pin "10") (pinfunction "B4_10") (pintype "bidirectional"))
    )
    (net (code "63") (name "RX") (class "Default")
      (node (ref "J17") (pin "P$3") (pinfunction "3_P$3") (pintype "passive"))
      (node (ref "U1") (pin "20") (pinfunction "PB11_20") (pintype "bidirectional"))
    )
    (net (code "64") (name "SCL1") (class "Default")
      (node (ref "J15") (pin "21") (pinfunction "21_21") (pintype "passive"))
      (node (ref "J15") (pin "22") (pinfunction "22_22") (pintype "passive"))
      (node (ref "J6") (pin "1") (pinfunction "1_1") (pintype "passive"))
      (node (ref "R13") (pin "2") (pinfunction "2_2") (pintype "passive"))
      (node (ref "U1") (pin "26") (pinfunction "PA17_26") (pintype "bidirectional"))
    )
    (net (code "65") (name "SCL2") (class "Default")
      (node (ref "J16") (pin "P$2") (pinfunction "2_P$2") (pintype "passive"))
      (node (ref "R15") (pin "2") (pinfunction "2_2") (pintype "passive"))
      (node (ref "U1") (pin "22") (pinfunction "PA13_22") (pintype "bidirectional"))
      (node (ref "U9") (pin "13") (pinfunction "AP_SCL/AP_SCLK_13") (pintype "input"))
    )
    (net (code "66") (name "SDA1") (class "Default")
      (node (ref "J15") (pin "23") (pinfunction "23_23") (pintype "passive"))
      (node (ref "J15") (pin "24") (pinfunction "24_24") (pintype "passive"))
      (node (ref "J6") (pin "2") (pinfunction "2_2") (pintype "passive"))
      (node (ref "R14") (pin "2") (pinfunction "2_2") (pintype "passive"))
      (node (ref "U1") (pin "25") (pinfunction "PA16_25") (pintype "bidirectional"))
    )
    (net (code "67") (name "SDA2") (class "Default")
      (node (ref "J16") (pin "P$3") (pinfunction "3_P$3") (pintype "passive"))
      (node (ref "R16") (pin "2") (pinfunction "2_2") (pintype "passive"))
      (node (ref "U1") (pin "21") (pinfunction "PA12_21") (pintype "bidirectional"))
      (node (ref "U9") (pin "14") (pinfunction "AP_SDA/AP_SDIO/AP_SDI_14") (pintype "bidirectional"))
    )
    (net (code "68") (name "SERVO1") (class "Default")
      (node (ref "J12") (pin "3") (pinfunction "3_3") (pintype "passive"))
      (node (ref "U1") (pin "1") (pinfunction "PA00_1") (pintype "bidirectional"))
    )
    (net (code "69") (name "SERVO2") (class "Default")
      (node (ref "J12") (pin "6") (pinfunction "6_6") (pintype "passive"))
      (node (ref "U1") (pin "2") (pinfunction "PA01_2") (pintype "bidirectional"))
    )
    (net (code "70") (name "SERVO3") (class "Default")
      (node (ref "J12") (pin "9") (pinfunction "9_9") (pintype "passive"))
      (node (ref "U1") (pin "13") (pinfunction "PA08_13") (pintype "bidirectional"))
    )
    (net (code "71") (name "SERVO4") (class "Default")
      (node (ref "J12") (pin "12") (pinfunction "12_12") (pintype "passive"))
      (node (ref "U1") (pin "14") (pinfunction "PA09_14") (pintype "bidirectional"))
    )
    (net (code "72") (name "SONAR1ECHO") (class "Default")
      (node (ref "U1") (pin "41") (pinfunction "PA28_41") (pintype "bidirectional"))
      (node (ref "U7") (pin "5") (pinfunction "A4_5") (pintype "bidirectional"))
    )
    (net (code "73") (name "SONAR1TRIG") (class "Default")
      (node (ref "J10") (pin "2") (pinfunction "2_2") (pintype "passive"))
      (node (ref "U1") (pin "39") (pinfunction "PA27_39") (pintype "bidirectional"))
    )
    (net (code "74") (name "SONAR2ECHO") (class "Default")
      (node (ref "U1") (pin "47") (pinfunction "PB02_47") (pintype "bidirectional"))
      (node (ref "U7") (pin "4") (pinfunction "A3_4") (pintype "bidirectional"))
    )
    (net (code "75") (name "SONAR2TRIG") (class "Default")
      (node (ref "J9") (pin "2") (pinfunction "2_2") (pintype "passive"))
      (node (ref "U1") (pin "38") (pinfunction "PB23_38") (pintype "bidirectional"))
    )
    (net (code "76") (name "SONAR3ECHO") (class "Default")
      (node (ref "U1") (pin "48") (pinfunction "PB03_48") (pintype "bidirectional"))
      (node (ref "U7") (pin "3") (pinfunction "A2_3") (pintype "bidirectional"))
    )
    (net (code "77") (name "SONAR3TRIG") (class "Default")
      (node (ref "J8") (pin "2") (pinfunction "2_2") (pintype "passive"))
      (node (ref "U1") (pin "37") (pinfunction "PB22_37") (pintype "bidirectional"))
    )
    (net (code "78") (name "SWCLK") (class "Default")
      (node (ref "R11") (pin "2") (pinfunction "2_2") (pintype "passive"))
      (node (ref "TP2") (pin "TP") (pinfunction "TP_TP") (pintype "input"))
      (node (ref "U1") (pin "45") (pinfunction "PA30_45") (pintype "bidirectional"))
    )
    (net (code "79") (name "SWDIO") (class "Default")
      (node (ref "TP3") (pin "TP") (pinfunction "TP_TP") (pintype "input"))
      (node (ref "U1") (pin "46") (pinfunction "PA31_46") (pintype "bidirectional"))
    )
    (net (code "80") (name "TX") (class "Default")
      (node (ref "J17") (pin "P$2") (pinfunction "2_P$2") (pintype "passive"))
      (node (ref "U1") (pin "19") (pinfunction "PB10_19") (pintype "bidirectional"))
    )
    (net (code "81") (name "VSENSE") (class "Default")
      (node (ref "R5") (pin "1") (pinfunction "1_1") (pintype "passive"))
      (node (ref "R6") (pin "1") (pinfunction "1_1") (pintype "passive"))
      (node (ref "U1") (pin "12") (pinfunction "PA07_12") (pintype "bidirectional"))
    )
    (net (code "82") (name "unconnected-(J15-Pad1)") (class "Default")
      (node (ref "J15") (pin "1") (pinfunction "1_1") (pintype "passive"))
    )
    (net (code "83") (name "unconnected-(J15-Pad5)") (class "Default")
      (node (ref "J15") (pin "5") (pinfunction "5_5") (pintype "passive"))
    )
    (net (code "84") (name "unconnected-(J17-4-PadP$4)") (class "Default")
      (node (ref "J17") (pin "P$4") (pinfunction "4_P$4") (pintype "passive"))
    )
    (net (code "85") (name "unconnected-(J17-5-PadP$5)") (class "Default")
      (node (ref "J17") (pin "P$5") (pinfunction "5_P$5") (pintype "passive"))
    )
    (net (code "86") (name "unconnected-(U1-PA03-Pad4)") (class "Default")
      (node (ref "U1") (pin "4") (pinfunction "PA03_4") (pintype "bidirectional"))
    )
    (net (code "87") (name "unconnected-(U1-PA11-Pad16)") (class "Default")
      (node (ref "U1") (pin "16") (pinfunction "PA11_16") (pintype "bidirectional"))
    )
    (net (code "88") (name "unconnected-(U7-A1-Pad2)") (class "Default")
      (node (ref "U7") (pin "2") (pinfunction "A1_2") (pintype "bidirectional"))
    )
    (net (code "89") (name "unconnected-(U7-B1-Pad13)") (class "Default")
      (node (ref "U7") (pin "13") (pinfunction "B1_13") (pintype "bidirectional"))
    )
    (net (code "90") (name "unconnected-(U7-NC-Pad9)") (class "Default")
      (node (ref "U7") (pin "9") (pinfunction "NC_9") (pintype "no_connect"))
    )
    (net (code "91") (name "unconnected-(U7-NC_2-Pad6)") (class "Default")
      (node (ref "U7") (pin "6") (pinfunction "NC_2_6") (pintype "no_connect"))
    )
    (net (code "92") (name "unconnected-(U9-INT1{slash}INT-Pad4)") (class "Default")
      (node (ref "U9") (pin "4") (pinfunction "INT1/INT_4") (pintype "output"))
    )
    (net (code "93") (name "unconnected-(U9-RESV_1-Pad2)") (class "Default")
      (node (ref "U9") (pin "2") (pinfunction "RESV_1_2") (pintype "bidirectional"))
    )
    (net (code "94") (name "unconnected-(U9-RESV_2-Pad3)") (class "Default")
      (node (ref "U9") (pin "3") (pinfunction "RESV_2_3") (pintype "bidirectional"))
    )
    (net (code "95") (name "unconnected-(U9-RESV_4-Pad10)") (class "Default")
      (node (ref "U9") (pin "10") (pinfunction "RESV_4_10") (pintype "bidirectional"))
    )
    (net (code "96") (name "unconnected-(U9-RESV_5-Pad11)") (class "Default")
      (node (ref "U9") (pin "11") (pinfunction "RESV_5_11") (pintype "bidirectional"))
    )
    (net (code "97") (name "unconnected-(USB1-ID-Pad4)") (class "Default")
      (node (ref "USB1") (pin "4") (pinfunction "ID_4") (pintype "bidirectional"))
    )
    (net (code "98") (name "unconnected-(USB1-VCC-Pad1)") (class "Default")
      (node (ref "USB1") (pin "1") (pinfunction "VCC_1") (pintype "bidirectional"))
    )
    (net (code "99") (name "~{RESET}") (class "Default")
      (node (ref "C14") (pin "1") (pinfunction "1_1") (pintype "passive"))
      (node (ref "J14") (pin "1") (pinfunction "1_1") (pintype "passive"))
      (node (ref "J14") (pin "2") (pinfunction "2_2") (pintype "passive"))
      (node (ref "R10") (pin "2") (pinfunction "2_2") (pintype "passive"))
      (node (ref "TP1") (pin "TP") (pinfunction "TP_TP") (pintype "input"))
      (node (ref "U1") (pin "40") (pinfunction "RSTN_40") (pintype "bidirectional"))
    )
  )
)
